# unt9833VCO_pots_jacks_1-29-23.net
KiCad netlist of a schematic drawn in EAGLE
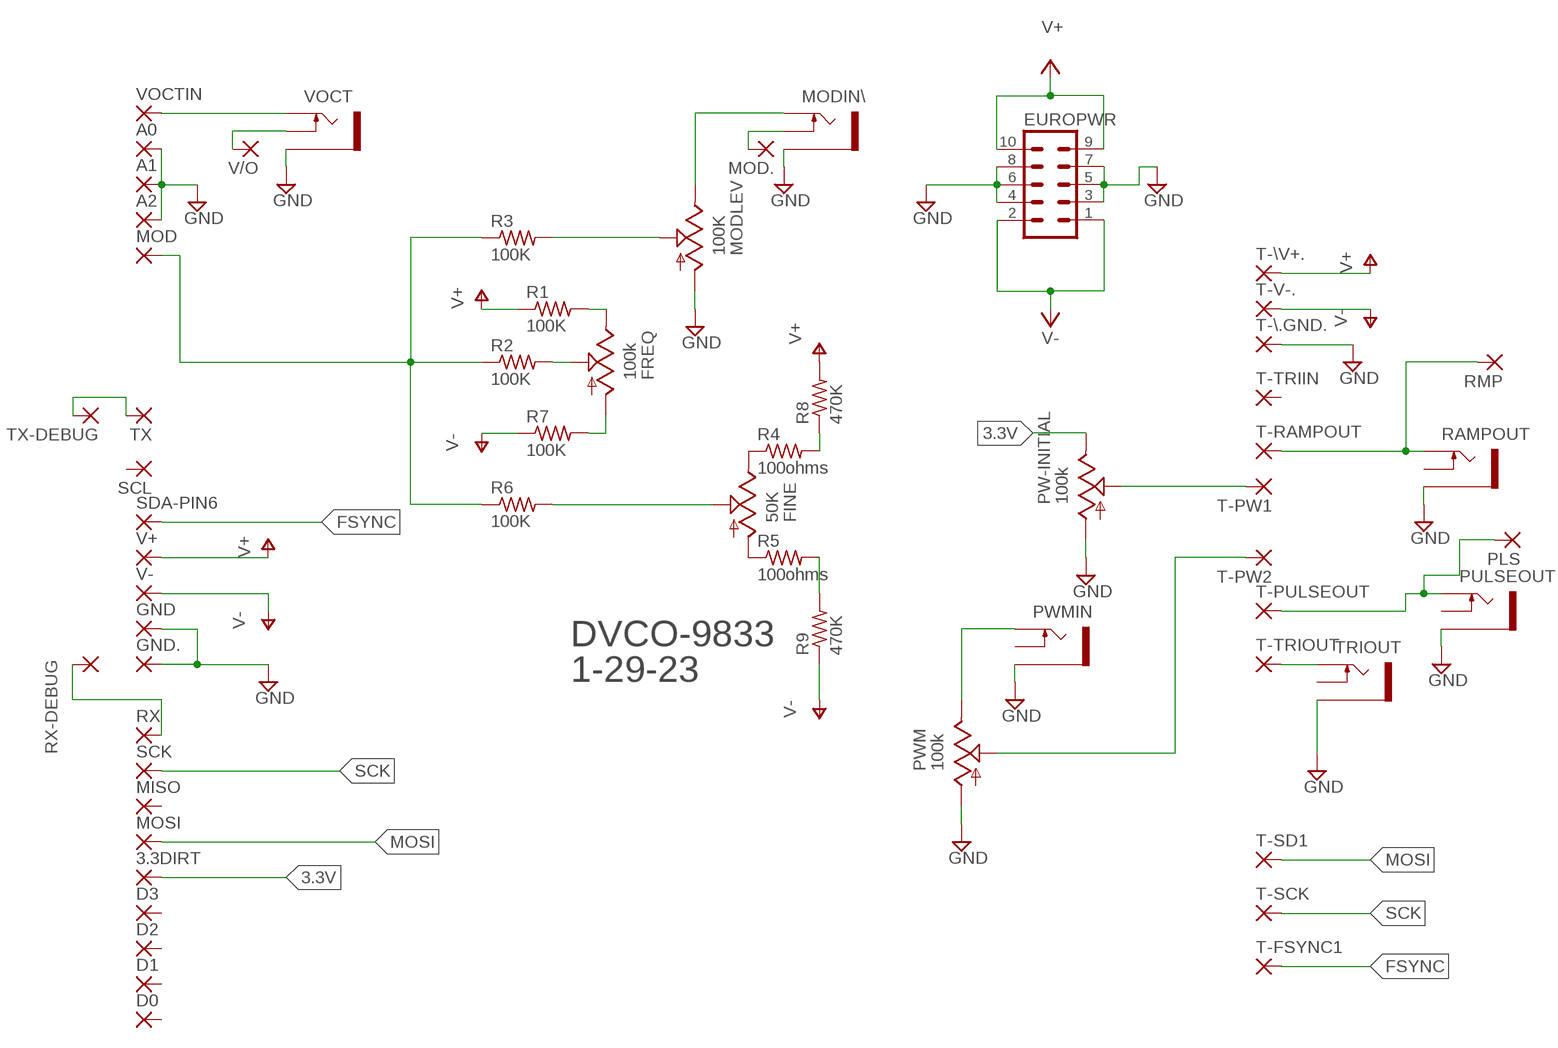
[diagram p0: schematic, sheet 1]

(export (version "E")
  (design (tool "Eeschema 10.0.6"))
  (components
    (comp (ref "3.3DIRT")
      (value "WIREPAD1,6/0,9")
      (footprint "eagle-import:1,6_0,9")
      (libsource (lib "eagle-import") (part "WIREPAD1,6/0,9"))
    )
    (comp (ref "A0")
      (value "WIREPAD1,6/0,9")
      (footprint "eagle-import:1,6_0,9")
      (libsource (lib "eagle-import") (part "WIREPAD1,6/0,9"))
    )
    (comp (ref "A1")
      (value "WIREPAD1,6/0,9")
      (footprint "eagle-import:1,6_0,9")
      (libsource (lib "eagle-import") (part "WIREPAD1,6/0,9"))
    )
    (comp (ref "A2")
      (value "WIREPAD1,6/0,9")
      (footprint "eagle-import:1,6_0,9")
      (libsource (lib "eagle-import") (part "WIREPAD1,6/0,9"))
    )
    (comp (ref "D0")
      (value "WIREPAD1,6/0,9")
      (footprint "eagle-import:1,6_0,9")
      (libsource (lib "eagle-import") (part "WIREPAD1,6/0,9"))
    )
    (comp (ref "D1")
      (value "WIREPAD1,6/0,9")
      (footprint "eagle-import:1,6_0,9")
      (libsource (lib "eagle-import") (part "WIREPAD1,6/0,9"))
    )
    (comp (ref "D2")
      (value "WIREPAD1,6/0,9")
      (footprint "eagle-import:1,6_0,9")
      (libsource (lib "eagle-import") (part "WIREPAD1,6/0,9"))
    )
    (comp (ref "D3")
      (value "WIREPAD1,6/0,9")
      (footprint "eagle-import:1,6_0,9")
      (libsource (lib "eagle-import") (part "WIREPAD1,6/0,9"))
    )
    (comp (ref "EUROPWR")
      (value "EURO_POWER_HEADERREGULAR")
      (footprint "eagle-import:EURO_POWER_HEADER")
      (libsource (lib "eagle-import") (part "EURO_POWER_HEADERREGULAR"))
    )
    (comp (ref "FINE")
      (value "50K")
      (footprint "eagle-import:9MM_SNAP-IN_POT")
      (libsource (lib "eagle-import") (part "9MM_SNAP-IN_POT_"))
    )
    (comp (ref "FREQ")
      (value "100k")
      (footprint "eagle-import:9MM_SNAP-IN_POT")
      (libsource (lib "eagle-import") (part "9MM_SNAP-IN_POT_"))
    )
    (comp (ref "GND")
      (value "WIREPAD1,6/0,9")
      (footprint "eagle-import:1,6_0,9")
      (libsource (lib "eagle-import") (part "WIREPAD1,6/0,9"))
    )
    (comp (ref "GND.")
      (value "WIREPAD1,6/0,9")
      (footprint "eagle-import:1,6_0,9")
      (libsource (lib "eagle-import") (part "WIREPAD1,6/0,9"))
    )
    (comp (ref "MISO")
      (value "WIREPAD1,6/0,9")
      (footprint "eagle-import:1,6_0,9")
      (libsource (lib "eagle-import") (part "WIREPAD1,6/0,9"))
    )
    (comp (ref "MOD")
      (value "WIREPAD1,6/0,9")
      (footprint "eagle-import:1,6_0,9")
      (libsource (lib "eagle-import") (part "WIREPAD1,6/0,9"))
    )
    (comp (ref "MOD.")
      (value "WIREPAD1,6/0,9")
      (footprint "eagle-import:1,6_0,9")
      (libsource (lib "eagle-import") (part "WIREPAD1,6/0,9"))
    )
    (comp (ref "MODIN\\")
      (value "THONKICONNNEW")
      (footprint "eagle-import:WQP-PJ301M-12_JACK")
      (libsource (lib "eagle-import") (part "THONKICONNNEW"))
    )
    (comp (ref "MODLEV")
      (value "100K")
      (footprint "eagle-import:9MM_SNAP-IN_POT")
      (libsource (lib "eagle-import") (part "9MM_SNAP-IN_POT_"))
    )
    (comp (ref "MOSI")
      (value "WIREPAD1,6/0,9")
      (footprint "eagle-import:1,6_0,9")
      (libsource (lib "eagle-import") (part "WIREPAD1,6/0,9"))
    )
    (comp (ref "PLS")
      (value "WIREPAD1,6/0,9")
      (footprint "eagle-import:1,6_0,9")
      (libsource (lib "eagle-import") (part "WIREPAD1,6/0,9"))
    )
    (comp (ref "PULSEOUT")
      (value "THONKICONNNEW")
      (footprint "eagle-import:WQP-PJ301M-12_JACK")
      (libsource (lib "eagle-import") (part "THONKICONNNEW"))
    )
    (comp (ref "PW-INITIAL")
      (value "100k")
      (footprint "eagle-import:9MM_SNAP-IN_POT")
      (libsource (lib "eagle-import") (part "9MM_SNAP-IN_POT_"))
    )
    (comp (ref "PWM")
      (value "100k")
      (footprint "eagle-import:9MM_SNAP-IN_POT")
      (libsource (lib "eagle-import") (part "9MM_SNAP-IN_POT_"))
    )
    (comp (ref "PWMIN")
      (value "THONKICONNNEW")
      (footprint "eagle-import:WQP-PJ301M-12_JACK")
      (libsource (lib "eagle-import") (part "THONKICONNNEW"))
    )
    (comp (ref "R1")
      (value "100K")
      (footprint "eagle-import:0204_7")
      (libsource (lib "eagle-import") (part "R-US_0204/7"))
    )
    (comp (ref "R2")
      (value "100K")
      (footprint "eagle-import:0207_15")
      (libsource (lib "eagle-import") (part "R-US_0207/15"))
    )
    (comp (ref "R3")
      (value "100K")
      (footprint "eagle-import:0207_15")
      (libsource (lib "eagle-import") (part "R-US_0207/15"))
    )
    (comp (ref "R4")
      (value "100ohms")
      (footprint "eagle-import:0207_15")
      (libsource (lib "eagle-import") (part "R-US_0207/15"))
    )
    (comp (ref "R5")
      (value "100ohms")
      (footprint "eagle-import:0207_15")
      (libsource (lib "eagle-import") (part "R-US_0207/15"))
    )
    (comp (ref "R6")
      (value "100K")
      (footprint "eagle-import:0207_15")
      (libsource (lib "eagle-import") (part "R-US_0207/15"))
    )
    (comp (ref "R7")
      (value "100K")
      (footprint "eagle-import:0204_7")
      (libsource (lib "eagle-import") (part "R-US_0204/7"))
    )
    (comp (ref "R8")
      (value "470K")
      (footprint "eagle-import:0204_7")
      (libsource (lib "eagle-import") (part "R-US_0204/7"))
    )
    (comp (ref "R9")
      (value "470K")
      (footprint "eagle-import:0204_7")
      (libsource (lib "eagle-import") (part "R-US_0204/7"))
    )
    (comp (ref "RAMPOUT")
      (value "THONKICONNNEW")
      (footprint "eagle-import:WQP-PJ301M-12_JACK")
      (libsource (lib "eagle-import") (part "THONKICONNNEW"))
    )
    (comp (ref "RMP")
      (value "WIREPAD1,6/0,9")
      (footprint "eagle-import:1,6_0,9")
      (libsource (lib "eagle-import") (part "WIREPAD1,6/0,9"))
    )
    (comp (ref "RX")
      (value "WIREPAD1,6/0,9")
      (footprint "eagle-import:1,6_0,9")
      (libsource (lib "eagle-import") (part "WIREPAD1,6/0,9"))
    )
    (comp (ref "RX-DEBUG")
      (value "WIREPAD1,6/0,9")
      (footprint "eagle-import:1,6_0,9")
      (libsource (lib "eagle-import") (part "WIREPAD1,6/0,9"))
    )
    (comp (ref "SCK")
      (value "WIREPAD1,6/0,9")
      (footprint "eagle-import:1,6_0,9")
      (libsource (lib "eagle-import") (part "WIREPAD1,6/0,9"))
    )
    (comp (ref "SCL")
      (value "WIREPAD1,6/0,9")
      (footprint "eagle-import:1,6_0,9")
      (libsource (lib "eagle-import") (part "WIREPAD1,6/0,9"))
    )
    (comp (ref "SDA-PIN6")
      (value "WIREPAD1,6/0,9")
      (footprint "eagle-import:1,6_0,9")
      (libsource (lib "eagle-import") (part "WIREPAD1,6/0,9"))
    )
    (comp (ref "T-FSYNC1")
      (value "WIREPAD1,6/0,9")
      (footprint "eagle-import:1,6_0,9")
      (libsource (lib "eagle-import") (part "WIREPAD1,6/0,9"))
    )
    (comp (ref "T-PULSEOUT")
      (value "WIREPAD1,6/0,9")
      (footprint "eagle-import:1,6_0,9")
      (libsource (lib "eagle-import") (part "WIREPAD1,6/0,9"))
    )
    (comp (ref "T-PW1")
      (value "WIREPAD1,6/0,9")
      (footprint "eagle-import:1,6_0,9")
      (libsource (lib "eagle-import") (part "WIREPAD1,6/0,9"))
    )
    (comp (ref "T-PW2")
      (value "WIREPAD1,6/0,9")
      (footprint "eagle-import:1,6_0,9")
      (libsource (lib "eagle-import") (part "WIREPAD1,6/0,9"))
    )
    (comp (ref "T-RAMPOUT")
      (value "WIREPAD1,6/0,9")
      (footprint "eagle-import:1,6_0,9")
      (libsource (lib "eagle-import") (part "WIREPAD1,6/0,9"))
    )
    (comp (ref "T-SCK")
      (value "WIREPAD1,6/0,9")
      (footprint "eagle-import:1,6_0,9")
      (libsource (lib "eagle-import") (part "WIREPAD1,6/0,9"))
    )
    (comp (ref "T-SD1")
      (value "WIREPAD1,6/0,9")
      (footprint "eagle-import:1,6_0,9")
      (libsource (lib "eagle-import") (part "WIREPAD1,6/0,9"))
    )
    (comp (ref "T-TRIIN")
      (value "WIREPAD1,6/0,9")
      (footprint "eagle-import:1,6_0,9")
      (libsource (lib "eagle-import") (part "WIREPAD1,6/0,9"))
    )
    (comp (ref "T-TRIOUT")
      (value "WIREPAD1,6/0,9")
      (footprint "eagle-import:1,6_0,9")
      (libsource (lib "eagle-import") (part "WIREPAD1,6/0,9"))
    )
    (comp (ref "T-V-.")
      (value "WIREPAD1,6/0,9")
      (footprint "eagle-import:1,6_0,9")
      (libsource (lib "eagle-import") (part "WIREPAD1,6/0,9"))
    )
    (comp (ref "T-\\.GND.")
      (value "WIREPAD1,6/0,9")
      (footprint "eagle-import:1,6_0,9")
      (libsource (lib "eagle-import") (part "WIREPAD1,6/0,9"))
    )
    (comp (ref "T-\\V+.")
      (value "WIREPAD1,6/0,9")
      (footprint "eagle-import:1,6_0,9")
      (libsource (lib "eagle-import") (part "WIREPAD1,6/0,9"))
    )
    (comp (ref "TRIOUT")
      (value "THONKICONNNEW")
      (footprint "eagle-import:WQP-PJ301M-12_JACK")
      (libsource (lib "eagle-import") (part "THONKICONNNEW"))
    )
    (comp (ref "TX")
      (value "WIREPAD1,6/0,9")
      (footprint "eagle-import:1,6_0,9")
      (libsource (lib "eagle-import") (part "WIREPAD1,6/0,9"))
    )
    (comp (ref "TX-DEBUG")
      (value "WIREPAD1,6/0,9")
      (footprint "eagle-import:1,6_0,9")
      (libsource (lib "eagle-import") (part "WIREPAD1,6/0,9"))
    )
    (comp (ref "V+")
      (value "WIREPAD1,6/0,9")
      (footprint "eagle-import:1,6_0,9")
      (libsource (lib "eagle-import") (part "WIREPAD1,6/0,9"))
    )
    (comp (ref "V-")
      (value "WIREPAD1,6/0,9")
      (footprint "eagle-import:1,6_0,9")
      (libsource (lib "eagle-import") (part "WIREPAD1,6/0,9"))
    )
    (comp (ref "V/O")
      (value "WIREPAD1,6/0,9")
      (footprint "eagle-import:1,6_0,9")
      (libsource (lib "eagle-import") (part "WIREPAD1,6/0,9"))
    )
    (comp (ref "VOCT")
      (value "THONKICONNNEW")
      (footprint "eagle-import:WQP-PJ301M-12_JACK")
      (libsource (lib "eagle-import") (part "THONKICONNNEW"))
    )
    (comp (ref "VOCTIN")
      (value "WIREPAD1,6/0,9")
      (footprint "eagle-import:1,6_0,9")
      (libsource (lib "eagle-import") (part "WIREPAD1,6/0,9"))
    )
  )
  (nets
    (net (code "1") (name "3.3V") (class "Default")
      (node (ref "3.3DIRT") (pin "1") (pinfunction "P_1") (pintype "passive"))
      (node (ref "PW-INITIAL") (pin "3") (pinfunction "E_3") (pintype "passive"))
    )
    (net (code "2") (name "FSYNC") (class "Default")
      (node (ref "SDA-PIN6") (pin "1") (pinfunction "P_1") (pintype "passive"))
      (node (ref "T-FSYNC1") (pin "1") (pinfunction "P_1") (pintype "passive"))
    )
    (net (code "3") (name "GND") (class "Default")
      (node (ref "A0") (pin "1") (pinfunction "P_1") (pintype "passive"))
      (node (ref "A1") (pin "1") (pinfunction "P_1") (pintype "passive"))
      (node (ref "A2") (pin "1") (pinfunction "P_1") (pintype "passive"))
      (node (ref "EUROPWR") (pin "3") (pinfunction "3_3") (pintype "passive"))
      (node (ref "EUROPWR") (pin "4") (pinfunction "4_4") (pintype "passive"))
      (node (ref "EUROPWR") (pin "5") (pinfunction "5_5") (pintype "passive"))
      (node (ref "EUROPWR") (pin "6") (pinfunction "6_6") (pintype "passive"))
      (node (ref "EUROPWR") (pin "7") (pinfunction "7_7") (pintype "passive"))
      (node (ref "EUROPWR") (pin "8") (pinfunction "8_8") (pintype "passive"))
      (node (ref "GND") (pin "1") (pinfunction "P_1") (pintype "passive"))
      (node (ref "GND.") (pin "1") (pinfunction "P_1") (pintype "passive"))
      (node (ref "MODIN\\") (pin "P$3_SLEEVE") (pinfunction "SLEEVE_P$3_SLEEVE") (pintype "passive"))
      (node (ref "MODLEV") (pin "1") (pinfunction "A_1") (pintype "passive"))
      (node (ref "PULSEOUT") (pin "P$3_SLEEVE") (pinfunction "SLEEVE_P$3_SLEEVE") (pintype "passive"))
      (node (ref "PW-INITIAL") (pin "1") (pinfunction "A_1") (pintype "passive"))
      (node (ref "PWM") (pin "1") (pinfunction "A_1") (pintype "passive"))
      (node (ref "PWMIN") (pin "P$3_SLEEVE") (pinfunction "SLEEVE_P$3_SLEEVE") (pintype "passive"))
      (node (ref "RAMPOUT") (pin "P$3_SLEEVE") (pinfunction "SLEEVE_P$3_SLEEVE") (pintype "passive"))
      (node (ref "T-\\.GND.") (pin "1") (pinfunction "P_1") (pintype "passive"))
      (node (ref "TRIOUT") (pin "P$3_SLEEVE") (pinfunction "SLEEVE_P$3_SLEEVE") (pintype "passive"))
      (node (ref "VOCT") (pin "P$3_SLEEVE") (pinfunction "SLEEVE_P$3_SLEEVE") (pintype "passive"))
    )
    (net (code "4") (name "MOSI") (class "Default")
      (node (ref "MOSI") (pin "1") (pinfunction "P_1") (pintype "passive"))
      (node (ref "T-SD1") (pin "1") (pinfunction "P_1") (pintype "passive"))
    )
    (net (code "5") (name "Net-(FINE-A)") (class "Default")
      (node (ref "FINE") (pin "1") (pinfunction "A_1") (pintype "passive"))
      (node (ref "R5") (pin "1") (pinfunction "1_1") (pintype "passive"))
    )
    (net (code "6") (name "Net-(FINE-E)") (class "Default")
      (node (ref "FINE") (pin "3") (pinfunction "E_3") (pintype "passive"))
      (node (ref "R4") (pin "1") (pinfunction "1_1") (pintype "passive"))
    )
    (net (code "7") (name "Net-(FINE-S)") (class "Default")
      (node (ref "FINE") (pin "2") (pinfunction "S_2") (pintype "passive"))
      (node (ref "R6") (pin "2") (pinfunction "2_2") (pintype "passive"))
    )
    (net (code "8") (name "Net-(FREQ-A)") (class "Default")
      (node (ref "FREQ") (pin "1") (pinfunction "A_1") (pintype "passive"))
      (node (ref "R7") (pin "2") (pinfunction "2_2") (pintype "passive"))
    )
    (net (code "9") (name "Net-(FREQ-E)") (class "Default")
      (node (ref "FREQ") (pin "3") (pinfunction "E_3") (pintype "passive"))
      (node (ref "R1") (pin "2") (pinfunction "2_2") (pintype "passive"))
    )
    (net (code "10") (name "Net-(FREQ-S)") (class "Default")
      (node (ref "FREQ") (pin "2") (pinfunction "S_2") (pintype "passive"))
      (node (ref "R2") (pin "2") (pinfunction "2_2") (pintype "passive"))
    )
    (net (code "11") (name "Net-(MOD-P)") (class "Default")
      (node (ref "MOD") (pin "1") (pinfunction "P_1") (pintype "passive"))
      (node (ref "R2") (pin "1") (pinfunction "1_1") (pintype "passive"))
      (node (ref "R3") (pin "1") (pinfunction "1_1") (pintype "passive"))
      (node (ref "R6") (pin "1") (pinfunction "1_1") (pintype "passive"))
    )
    (net (code "12") (name "Net-(MOD.-P)") (class "Default")
      (node (ref "MOD.") (pin "1") (pinfunction "P_1") (pintype "passive"))
      (node (ref "MODIN\\") (pin "P$2_SWITCH") (pinfunction "SWITCH_P$2_SWITCH") (pintype "passive"))
    )
    (net (code "13") (name "Net-(MODIN\\-TIP)") (class "Default")
      (node (ref "MODIN\\") (pin "P$1_TIP") (pinfunction "TIP_P$1_TIP") (pintype "passive"))
      (node (ref "MODLEV") (pin "3") (pinfunction "E_3") (pintype "passive"))
    )
    (net (code "14") (name "Net-(MODLEV-S)") (class "Default")
      (node (ref "MODLEV") (pin "2") (pinfunction "S_2") (pintype "passive"))
      (node (ref "R3") (pin "2") (pinfunction "2_2") (pintype "passive"))
    )
    (net (code "15") (name "Net-(PLS-P)") (class "Default")
      (node (ref "PLS") (pin "1") (pinfunction "P_1") (pintype "passive"))
      (node (ref "PULSEOUT") (pin "P$1_TIP") (pinfunction "TIP_P$1_TIP") (pintype "passive"))
      (node (ref "T-PULSEOUT") (pin "1") (pinfunction "P_1") (pintype "passive"))
    )
    (net (code "16") (name "Net-(PW-INITIAL-S)") (class "Default")
      (node (ref "PW-INITIAL") (pin "2") (pinfunction "S_2") (pintype "passive"))
      (node (ref "T-PW1") (pin "1") (pinfunction "P_1") (pintype "passive"))
    )
    (net (code "17") (name "Net-(PWM-E)") (class "Default")
      (node (ref "PWM") (pin "3") (pinfunction "E_3") (pintype "passive"))
      (node (ref "PWMIN") (pin "P$1_TIP") (pinfunction "TIP_P$1_TIP") (pintype "passive"))
    )
    (net (code "18") (name "Net-(PWM-S)") (class "Default")
      (node (ref "PWM") (pin "2") (pinfunction "S_2") (pintype "passive"))
      (node (ref "T-PW2") (pin "1") (pinfunction "P_1") (pintype "passive"))
    )
    (net (code "19") (name "Net-(R4-Pad2)") (class "Default")
      (node (ref "R4") (pin "2") (pinfunction "2_2") (pintype "passive"))
      (node (ref "R8") (pin "1") (pinfunction "1_1") (pintype "passive"))
    )
    (net (code "20") (name "Net-(R5-Pad2)") (class "Default")
      (node (ref "R5") (pin "2") (pinfunction "2_2") (pintype "passive"))
      (node (ref "R9") (pin "2") (pinfunction "2_2") (pintype "passive"))
    )
    (net (code "21") (name "Net-(RAMPOUT-TIP)") (class "Default")
      (node (ref "RAMPOUT") (pin "P$1_TIP") (pinfunction "TIP_P$1_TIP") (pintype "passive"))
      (node (ref "RMP") (pin "1") (pinfunction "P_1") (pintype "passive"))
      (node (ref "T-RAMPOUT") (pin "1") (pinfunction "P_1") (pintype "passive"))
    )
    (net (code "22") (name "Net-(RX-DEBUG-P)") (class "Default")
      (node (ref "RX") (pin "1") (pinfunction "P_1") (pintype "passive"))
      (node (ref "RX-DEBUG") (pin "1") (pinfunction "P_1") (pintype "passive"))
    )
    (net (code "23") (name "Net-(T-TRIOUT-P)") (class "Default")
      (node (ref "T-TRIOUT") (pin "1") (pinfunction "P_1") (pintype "passive"))
      (node (ref "TRIOUT") (pin "P$1_TIP") (pinfunction "TIP_P$1_TIP") (pintype "passive"))
    )
    (net (code "24") (name "Net-(TX-DEBUG-P)") (class "Default")
      (node (ref "TX") (pin "1") (pinfunction "P_1") (pintype "passive"))
      (node (ref "TX-DEBUG") (pin "1") (pinfunction "P_1") (pintype "passive"))
    )
    (net (code "25") (name "Net-(V/O-P)") (class "Default")
      (node (ref "V/O") (pin "1") (pinfunction "P_1") (pintype "passive"))
      (node (ref "VOCT") (pin "P$2_SWITCH") (pinfunction "SWITCH_P$2_SWITCH") (pintype "passive"))
    )
    (net (code "26") (name "Net-(VOCT-TIP)") (class "Default")
      (node (ref "VOCT") (pin "P$1_TIP") (pinfunction "TIP_P$1_TIP") (pintype "passive"))
      (node (ref "VOCTIN") (pin "1") (pinfunction "P_1") (pintype "passive"))
    )
    (net (code "27") (name "SCK") (class "Default")
      (node (ref "SCK") (pin "1") (pinfunction "P_1") (pintype "passive"))
      (node (ref "T-SCK") (pin "1") (pinfunction "P_1") (pintype "passive"))
    )
    (net (code "28") (name "V+") (class "Default")
      (node (ref "EUROPWR") (pin "10") (pinfunction "10_10") (pintype "passive"))
      (node (ref "EUROPWR") (pin "9") (pinfunction "9_9") (pintype "passive"))
      (node (ref "R1") (pin "1") (pinfunction "1_1") (pintype "passive"))
      (node (ref "R8") (pin "2") (pinfunction "2_2") (pintype "passive"))
      (node (ref "T-\\V+.") (pin "1") (pinfunction "P_1") (pintype "passive"))
      (node (ref "V+") (pin "1") (pinfunction "P_1") (pintype "passive"))
    )
    (net (code "29") (name "V-") (class "Default")
      (node (ref "EUROPWR") (pin "1") (pinfunction "1_1") (pintype "passive"))
      (node (ref "EUROPWR") (pin "2") (pinfunction "2_2") (pintype "passive"))
      (node (ref "R7") (pin "1") (pinfunction "1_1") (pintype "passive"))
      (node (ref "R9") (pin "1") (pinfunction "1_1") (pintype "passive"))
      (node (ref "T-V-.") (pin "1") (pinfunction "P_1") (pintype "passive"))
      (node (ref "V-") (pin "1") (pinfunction "P_1") (pintype "passive"))
    )
    (net (code "30") (name "unconnected-(D0-P-Pad1)") (class "Default")
      (node (ref "D0") (pin "1") (pinfunction "P_1") (pintype "passive"))
    )
    (net (code "31") (name "unconnected-(D1-P-Pad1)") (class "Default")
      (node (ref "D1") (pin "1") (pinfunction "P_1") (pintype "passive"))
    )
    (net (code "32") (name "unconnected-(D2-P-Pad1)") (class "Default")
      (node (ref "D2") (pin "1") (pinfunction "P_1") (pintype "passive"))
    )
    (net (code "33") (name "unconnected-(D3-P-Pad1)") (class "Default")
      (node (ref "D3") (pin "1") (pinfunction "P_1") (pintype "passive"))
    )
    (net (code "34") (name "unconnected-(MISO-P-Pad1)") (class "Default")
      (node (ref "MISO") (pin "1") (pinfunction "P_1") (pintype "passive"))
    )
    (net (code "35") (name "unconnected-(PULSEOUT-SWITCH-PadP$2_SWITCH)") (class "Default")
      (node (ref "PULSEOUT") (pin "P$2_SWITCH") (pinfunction "SWITCH_P$2_SWITCH") (pintype "passive"))
    )
    (net (code "36") (name "unconnected-(PWMIN-SWITCH-PadP$2_SWITCH)") (class "Default")
      (node (ref "PWMIN") (pin "P$2_SWITCH") (pinfunction "SWITCH_P$2_SWITCH") (pintype "passive"))
    )
    (net (code "37") (name "unconnected-(RAMPOUT-SWITCH-PadP$2_SWITCH)") (class "Default")
      (node (ref "RAMPOUT") (pin "P$2_SWITCH") (pinfunction "SWITCH_P$2_SWITCH") (pintype "passive"))
    )
    (net (code "38") (name "unconnected-(SCL-P-Pad1)") (class "Default")
      (node (ref "SCL") (pin "1") (pinfunction "P_1") (pintype "passive"))
    )
    (net (code "39") (name "unconnected-(T-TRIIN-P-Pad1)") (class "Default")
      (node (ref "T-TRIIN") (pin "1") (pinfunction "P_1") (pintype "passive"))
    )
    (net (code "40") (name "unconnected-(TRIOUT-SWITCH-PadP$2_SWITCH)") (class "Default")
      (node (ref "TRIOUT") (pin "P$2_SWITCH") (pinfunction "SWITCH_P$2_SWITCH") (pintype "passive"))
    )
  )
)
